# 03_Power_Amp.net
KiCad netlist of a schematic drawn in Altium Designer
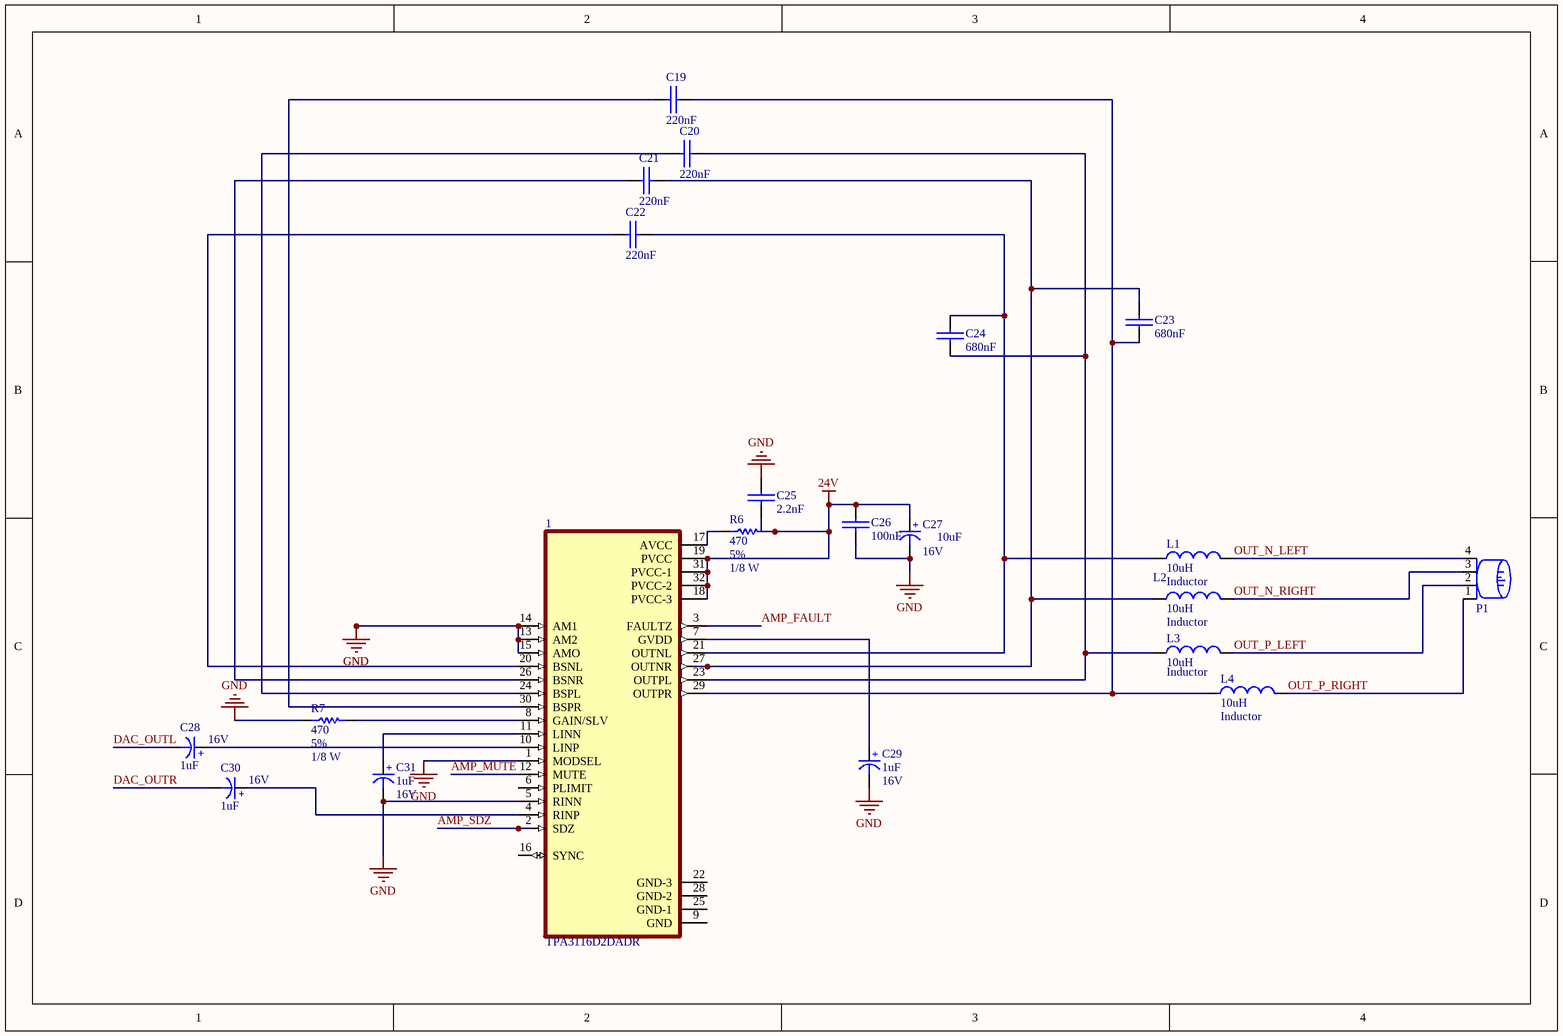
[diagram p0: 03_Power_Amp.SchDoc]

(export (version "E")
  (design (tool "Eeschema 10.0.6"))
  (components
    (comp (ref "1")
      (value "TPA3116D2DADR")
      (footprint "SOP65P810X115-33N")
      (fields (field (name "MF") "Texas Instruments"))
      (libsource (lib "TPA3116D2DADR") (part "TPA3116D2DADR"))
    )
    (comp (ref "C19")
      (value "220nF")
      (footprint "SMD_CAP_1206")
      (description "Bipolar Capacitor")
      (fields (field (name "VOLTAGE") "100V") (field (name "DESIGNER") "Saeid Jorablo"))
      (libsource (lib "My Library") (part "Cap-Bipolar"))
    )
    (comp (ref "C20")
      (value "220nF")
      (footprint "SMD_CAP_1206")
      (description "Bipolar Capacitor")
      (fields (field (name "VOLTAGE") "100V") (field (name "DESIGNER") "Saeid Jorablo"))
      (libsource (lib "My Library") (part "Cap-Bipolar"))
    )
    (comp (ref "C21")
      (value "220nF")
      (footprint "SMD_CAP_1206")
      (description "Bipolar Capacitor")
      (fields (field (name "VOLTAGE") "100V") (field (name "DESIGNER") "Saeid Jorablo"))
      (libsource (lib "My Library") (part "Cap-Bipolar"))
    )
    (comp (ref "C22")
      (value "220nF")
      (footprint "SMD_CAP_1206")
      (description "Bipolar Capacitor")
      (fields (field (name "VOLTAGE") "100V") (field (name "DESIGNER") "Saeid Jorablo"))
      (libsource (lib "My Library") (part "Cap-Bipolar"))
    )
    (comp (ref "C23")
      (value "680nF")
      (footprint "SMD_CAP_1206")
      (description "Bipolar Capacitor")
      (fields (field (name "VOLTAGE") "100V") (field (name "DESIGNER") "Saeid Jorablo"))
      (libsource (lib "My Library") (part "Cap-Bipolar"))
    )
    (comp (ref "C24")
      (value "680nF")
      (footprint "SMD_CAP_1206")
      (description "Bipolar Capacitor")
      (fields (field (name "VOLTAGE") "100V") (field (name "DESIGNER") "Saeid Jorablo"))
      (libsource (lib "My Library") (part "Cap-Bipolar"))
    )
    (comp (ref "C25")
      (value "2.2nF")
      (footprint "SMD_CAP_1206")
      (description "Bipolar Capacitor")
      (fields (field (name "VOLTAGE") "100V") (field (name "DESIGNER") "Saeid Jorablo"))
      (libsource (lib "My Library") (part "Cap-Bipolar"))
    )
    (comp (ref "C26")
      (value "100nF")
      (footprint "SMD_CAP_1206")
      (description "Bipolar Capacitor")
      (fields (field (name "VOLTAGE") "100V") (field (name "DESIGNER") "Saeid Jorablo"))
      (libsource (lib "My Library") (part "Cap-Bipolar"))
    )
    (comp (ref "C27")
      (value "10uF")
      (footprint "cap 01")
      (description "Polar Capacitor")
      (fields (field (name "VOLTAGE") "16V") (field (name "DESIGNER") "Saeid Jorablo"))
      (libsource (lib "My Library") (part "Cap-Polar"))
    )
    (comp (ref "C28")
      (value "1uF")
      (footprint "cap 01")
      (description "Polar Capacitor")
      (fields (field (name "VOLTAGE") "16V") (field (name "DESIGNER") "Saeid Jorablo"))
      (libsource (lib "My Library") (part "Cap-Polar"))
    )
    (comp (ref "C29")
      (value "1uF")
      (footprint "cap 01")
      (description "Polar Capacitor")
      (fields (field (name "VOLTAGE") "16V") (field (name "DESIGNER") "Saeid Jorablo"))
      (libsource (lib "My Library") (part "Cap-Polar"))
    )
    (comp (ref "C30")
      (value "1uF")
      (footprint "cap 01")
      (description "Polar Capacitor")
      (fields (field (name "VOLTAGE") "16V") (field (name "DESIGNER") "Saeid Jorablo"))
      (libsource (lib "My Library") (part "Cap-Polar"))
    )
    (comp (ref "C31")
      (value "1uF")
      (footprint "cap 01")
      (description "Polar Capacitor")
      (fields (field (name "VOLTAGE") "16V") (field (name "DESIGNER") "Saeid Jorablo"))
      (libsource (lib "My Library") (part "Cap-Polar"))
    )
    (comp (ref "L1")
      (value "Inductor")
      (footprint "INDC1608L")
      (fields (field (name "ALTIUM_VALUE") "10uH") (field (name "PUBLISHER") "Altium Limited"))
      (libsource (lib "My Library") (part "Inductor"))
    )
    (comp (ref "L2")
      (value "Inductor")
      (footprint "INDC1608L")
      (fields (field (name "ALTIUM_VALUE") "10uH") (field (name "PUBLISHER") "Altium Limited"))
      (libsource (lib "My Library") (part "Inductor"))
    )
    (comp (ref "L3")
      (value "Inductor")
      (footprint "INDC1608L")
      (fields (field (name "ALTIUM_VALUE") "10uH") (field (name "PUBLISHER") "Altium Limited"))
      (libsource (lib "My Library") (part "Inductor"))
    )
    (comp (ref "L4")
      (value "Inductor")
      (footprint "INDC1608L")
      (fields (field (name "ALTIUM_VALUE") "10uH") (field (name "PUBLISHER") "Altium Limited"))
      (libsource (lib "My Library") (part "Inductor"))
    )
    (comp (ref "P1")
      (value "Socket 4 Pin")
      (footprint "4pin")
      (description "Power Input")
      (libsource (lib "My Library") (part "Socket 4 Pin"))
    )
    (comp (ref "R6")
      (value "470")
      (footprint "RES 0805 (2012X06L)")
      (description "Resistor")
      (fields (field (name "TOLERANCE") "5%") (field (name "POWER") "1/8 W"))
      (libsource (lib "My Library") (part "Resistor"))
    )
    (comp (ref "R7")
      (value "470")
      (footprint "RES 0805 (2012X06L)")
      (description "Resistor")
      (fields (field (name "TOLERANCE") "5%") (field (name "POWER") "1/8 W"))
      (libsource (lib "My Library") (part "Resistor"))
    )
  )
  (nets
    (net (code "1") (name "/AMP_FAULT") (class "Default")
      (node (ref "1") (pin "3") (pinfunction "FAULTZ_3") (pintype "output"))
    )
    (net (code "2") (name "/AMP_MUTE") (class "Default")
      (node (ref "1") (pin "12") (pinfunction "MUTE_12") (pintype "input"))
    )
    (net (code "3") (name "/AMP_SDZ") (class "Default")
      (node (ref "1") (pin "2") (pinfunction "SDZ_2") (pintype "input"))
    )
    (net (code "4") (name "/DAC_OUTL") (class "Default")
      (node (ref "C28") (pin "2") (pinfunction "-_2") (pintype "passive"))
    )
    (net (code "5") (name "/DAC_OUTR") (class "Default")
      (node (ref "C30") (pin "2") (pinfunction "-_2") (pintype "passive"))
    )
    (net (code "6") (name "/OUT_N_LEFT") (class "Default")
      (node (ref "L1") (pin "2") (pinfunction "2_2") (pintype "passive"))
      (node (ref "P1") (pin "4") (pinfunction "4_4") (pintype "passive"))
    )
    (net (code "7") (name "/OUT_N_RIGHT") (class "Default")
      (node (ref "L2") (pin "2") (pinfunction "2_2") (pintype "passive"))
      (node (ref "P1") (pin "3") (pinfunction "3_3") (pintype "passive"))
    )
    (net (code "8") (name "/OUT_P_LEFT") (class "Default")
      (node (ref "L3") (pin "2") (pinfunction "2_2") (pintype "passive"))
      (node (ref "P1") (pin "2") (pinfunction "2_2") (pintype "passive"))
    )
    (net (code "9") (name "/OUT_P_RIGHT") (class "Default")
      (node (ref "L4") (pin "2") (pinfunction "2_2") (pintype "passive"))
      (node (ref "P1") (pin "1") (pinfunction "1_1") (pintype "passive"))
    )
    (net (code "10") (name "24V") (class "Default")
      (node (ref "1") (pin "18") (pinfunction "PVCC-3_18") (pintype "power_in"))
      (node (ref "1") (pin "19") (pinfunction "PVCC_19") (pintype "power_in"))
      (node (ref "1") (pin "31") (pinfunction "PVCC-1_31") (pintype "power_in"))
      (node (ref "1") (pin "32") (pinfunction "PVCC-2_32") (pintype "power_in"))
      (node (ref "C25") (pin "2") (pinfunction "-_2") (pintype "passive"))
      (node (ref "C26") (pin "2") (pinfunction "-_2") (pintype "passive"))
      (node (ref "C27") (pin "1") (pinfunction "+_1") (pintype "passive"))
      (node (ref "R6") (pin "2") (pinfunction "2_2") (pintype "passive"))
    )
    (net (code "11") (name "GND") (class "Default")
      (node (ref "1") (pin "1") (pinfunction "MODSEL_1") (pintype "input"))
      (node (ref "1") (pin "13") (pinfunction "AM2_13") (pintype "input"))
      (node (ref "1") (pin "14") (pinfunction "AM1_14") (pintype "input"))
      (node (ref "1") (pin "15") (pinfunction "AMO_15") (pintype "input"))
      (node (ref "1") (pin "5") (pinfunction "RINN_5") (pintype "input"))
      (node (ref "C25") (pin "1") (pinfunction "+_1") (pintype "passive"))
      (node (ref "C26") (pin "1") (pinfunction "+_1") (pintype "passive"))
      (node (ref "C27") (pin "2") (pinfunction "-_2") (pintype "passive"))
      (node (ref "C29") (pin "2") (pinfunction "-_2") (pintype "passive"))
      (node (ref "C31") (pin "2") (pinfunction "-_2") (pintype "passive"))
      (node (ref "R7") (pin "1") (pinfunction "1_1") (pintype "passive"))
    )
    (net (code "12") (name "Net-(1-AVCC)") (class "Default")
      (node (ref "1") (pin "17") (pinfunction "AVCC_17") (pintype "power_in"))
      (node (ref "R6") (pin "1") (pinfunction "1_1") (pintype "passive"))
    )
    (net (code "13") (name "Net-(1-BSNL)") (class "Default")
      (node (ref "1") (pin "20") (pinfunction "BSNL_20") (pintype "input"))
      (node (ref "C22") (pin "2") (pinfunction "-_2") (pintype "passive"))
    )
    (net (code "14") (name "Net-(1-BSNR)") (class "Default")
      (node (ref "1") (pin "26") (pinfunction "BSNR_26") (pintype "input"))
      (node (ref "C21") (pin "2") (pinfunction "-_2") (pintype "passive"))
    )
    (net (code "15") (name "Net-(1-BSPL)") (class "Default")
      (node (ref "1") (pin "24") (pinfunction "BSPL_24") (pintype "input"))
      (node (ref "C20") (pin "2") (pinfunction "-_2") (pintype "passive"))
    )
    (net (code "16") (name "Net-(1-BSPR)") (class "Default")
      (node (ref "1") (pin "30") (pinfunction "BSPR_30") (pintype "input"))
      (node (ref "C19") (pin "2") (pinfunction "-_2") (pintype "passive"))
    )
    (net (code "17") (name "Net-(1-GAIN{slash}SLV)") (class "Default")
      (node (ref "1") (pin "8") (pinfunction "GAIN/SLV_8") (pintype "input"))
      (node (ref "R7") (pin "2") (pinfunction "2_2") (pintype "passive"))
    )
    (net (code "18") (name "Net-(1-GVDD)") (class "Default")
      (node (ref "1") (pin "7") (pinfunction "GVDD_7") (pintype "output"))
      (node (ref "C29") (pin "1") (pinfunction "+_1") (pintype "passive"))
    )
    (net (code "19") (name "Net-(1-LINN)") (class "Default")
      (node (ref "1") (pin "11") (pinfunction "LINN_11") (pintype "input"))
      (node (ref "C31") (pin "1") (pinfunction "+_1") (pintype "passive"))
    )
    (net (code "20") (name "Net-(1-LINP)") (class "Default")
      (node (ref "1") (pin "10") (pinfunction "LINP_10") (pintype "input"))
      (node (ref "C28") (pin "1") (pinfunction "+_1") (pintype "passive"))
    )
    (net (code "21") (name "Net-(1-OUTNL)") (class "Default")
      (node (ref "1") (pin "21") (pinfunction "OUTNL_21") (pintype "output"))
      (node (ref "C22") (pin "1") (pinfunction "+_1") (pintype "passive"))
      (node (ref "C24") (pin "2") (pinfunction "-_2") (pintype "passive"))
      (node (ref "L1") (pin "1") (pinfunction "1_1") (pintype "passive"))
    )
    (net (code "22") (name "Net-(1-OUTNR)") (class "Default")
      (node (ref "1") (pin "27") (pinfunction "OUTNR_27") (pintype "output"))
      (node (ref "C21") (pin "1") (pinfunction "+_1") (pintype "passive"))
      (node (ref "C23") (pin "2") (pinfunction "-_2") (pintype "passive"))
      (node (ref "L2") (pin "1") (pinfunction "1_1") (pintype "passive"))
    )
    (net (code "23") (name "Net-(1-OUTPL)") (class "Default")
      (node (ref "1") (pin "23") (pinfunction "OUTPL_23") (pintype "output"))
      (node (ref "C20") (pin "1") (pinfunction "+_1") (pintype "passive"))
      (node (ref "C24") (pin "1") (pinfunction "+_1") (pintype "passive"))
      (node (ref "L3") (pin "1") (pinfunction "1_1") (pintype "passive"))
    )
    (net (code "24") (name "Net-(1-OUTPR)") (class "Default")
      (node (ref "1") (pin "29") (pinfunction "OUTPR_29") (pintype "output"))
      (node (ref "C19") (pin "1") (pinfunction "+_1") (pintype "passive"))
      (node (ref "C23") (pin "1") (pinfunction "+_1") (pintype "passive"))
      (node (ref "L4") (pin "1") (pinfunction "1_1") (pintype "passive"))
    )
    (net (code "25") (name "Net-(1-RINP)") (class "Default")
      (node (ref "1") (pin "4") (pinfunction "RINP_4") (pintype "input"))
      (node (ref "C30") (pin "1") (pinfunction "+_1") (pintype "passive"))
    )
    (net (code "26") (name "unconnected-(1-GND-1-Pad25)") (class "Default")
      (node (ref "1") (pin "25") (pinfunction "GND-1_25") (pintype "power_in"))
    )
    (net (code "27") (name "unconnected-(1-GND-2-Pad28)") (class "Default")
      (node (ref "1") (pin "28") (pinfunction "GND-2_28") (pintype "power_in"))
    )
    (net (code "28") (name "unconnected-(1-GND-3-Pad22)") (class "Default")
      (node (ref "1") (pin "22") (pinfunction "GND-3_22") (pintype "power_in"))
    )
    (net (code "29") (name "unconnected-(1-GND-Pad9)") (class "Default")
      (node (ref "1") (pin "9") (pinfunction "GND_9") (pintype "power_in"))
    )
    (net (code "30") (name "unconnected-(1-PLIMIT-Pad6)") (class "Default")
      (node (ref "1") (pin "6") (pinfunction "PLIMIT_6") (pintype "input"))
    )
    (net (code "31") (name "unconnected-(1-SYNC-Pad16)") (class "Default")
      (node (ref "1") (pin "16") (pinfunction "SYNC_16") (pintype "bidirectional"))
    )
  )
)
